# PCB-TBAR-BORADC.net
KiCad netlist of a schematic drawn in EAGLE
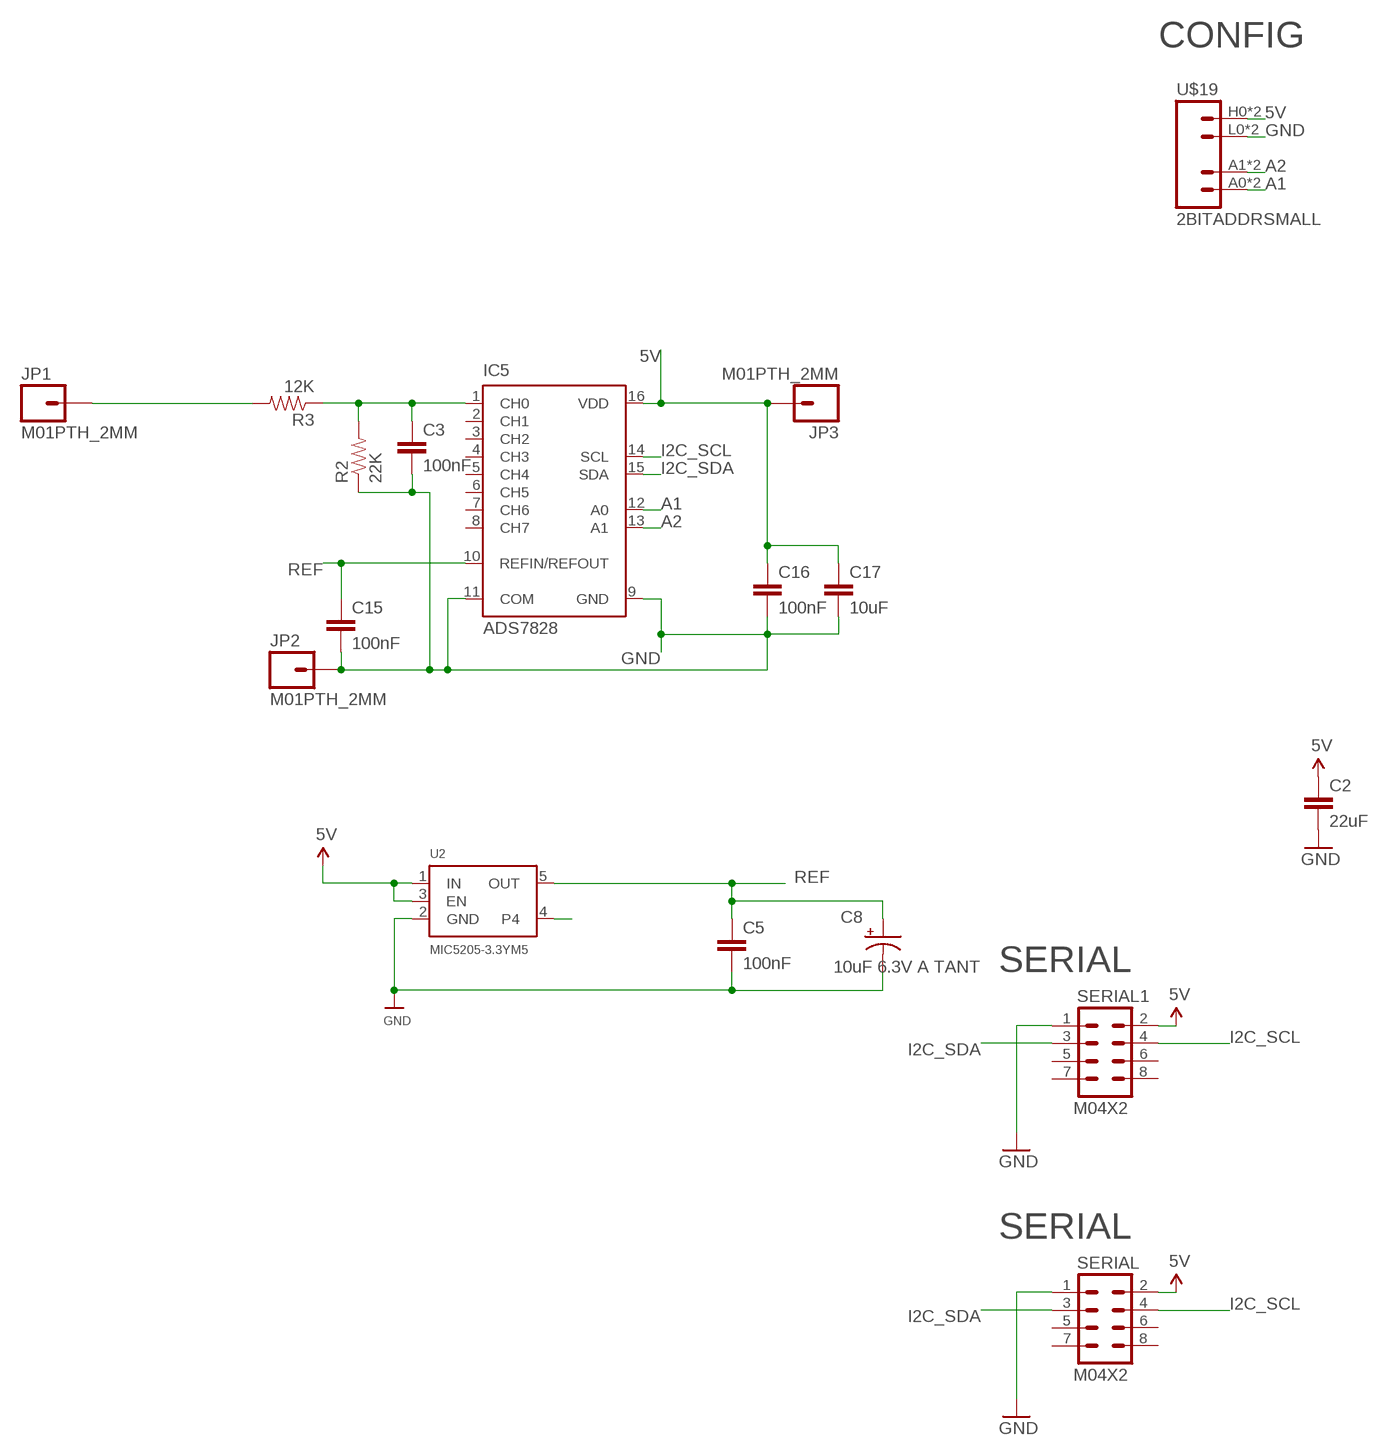
[diagram p0: schematic, sheet 1]

(export (version "E")
  (design (tool "Eeschema 10.0.6"))
  (components
    (comp (ref "C2")
      (value "22uF")
      (footprint "eagle-import:0805")
      (libsource (lib "eagle-import") (part "CAP0805"))
    )
    (comp (ref "C3")
      (value "100nF")
      (footprint "eagle-import:0603-CAP")
      (libsource (lib "eagle-import") (part "CAP0603-CAP"))
    )
    (comp (ref "C5")
      (value "100nF")
      (footprint "eagle-import:0603-CAP")
      (libsource (lib "eagle-import") (part "CAP0603-CAP"))
    )
    (comp (ref "C8")
      (value "10uF 6.3V A TANT")
      (footprint "eagle-import:EIA3216")
      (libsource (lib "eagle-import") (part "CAP_POL1206"))
    )
    (comp (ref "C15")
      (value "100nF")
      (footprint "eagle-import:0603-CAP")
      (libsource (lib "eagle-import") (part "CAP0603-CAP"))
    )
    (comp (ref "C16")
      (value "100nF")
      (footprint "eagle-import:0603-CAP")
      (libsource (lib "eagle-import") (part "CAP0603-CAP"))
    )
    (comp (ref "C17")
      (value "10uF")
      (footprint "eagle-import:0805")
      (libsource (lib "eagle-import") (part "CAP0805"))
    )
    (comp (ref "IC5")
      (value "ADS7828")
      (footprint "eagle-import:TSSOP16-PW")
      (fields (field (name "MF") "TEXAS INSTRUMENTS") (field (name "MPN") "ADS7828E/250"))
      (libsource (lib "eagle-import") (part "ADS7828"))
    )
    (comp (ref "JP1")
      (value "M01PTH_2MM")
      (footprint "eagle-import:1X01_2MM")
      (libsource (lib "eagle-import") (part "M01PTH_2MM"))
    )
    (comp (ref "JP2")
      (value "M01PTH_2MM")
      (footprint "eagle-import:1X01_2MM")
      (libsource (lib "eagle-import") (part "M01PTH_2MM"))
    )
    (comp (ref "JP3")
      (value "M01PTH_2MM")
      (footprint "eagle-import:1X01_2MM")
      (libsource (lib "eagle-import") (part "M01PTH_2MM"))
    )
    (comp (ref "R2")
      (value "22K")
      (footprint "eagle-import:0603-RES")
      (libsource (lib "eagle-import") (part "RESISTOR0603-RES"))
    )
    (comp (ref "R3")
      (value "12K")
      (footprint "eagle-import:0603-RES")
      (libsource (lib "eagle-import") (part "RESISTOR0603-RES"))
    )
    (comp (ref "SERIAL")
      (value "M04X2")
      (footprint "eagle-import:2X4")
      (libsource (lib "eagle-import") (part "M04X2"))
    )
    (comp (ref "SERIAL1")
      (value "M04X2")
      (footprint "eagle-import:2X4")
      (libsource (lib "eagle-import") (part "M04X2"))
    )
    (comp (ref "U$19")
      (value "2BITADDRSMALL")
      (footprint "eagle-import:2BITADDR_SMALL")
      (libsource (lib "eagle-import") (part "2BITADDRSMALL"))
    )
    (comp (ref "U2")
      (value "MIC5205-3.3YM5")
      (footprint "eagle-import:SOT23-5")
      (libsource (lib "eagle-import") (part "VREG_SOT23-5"))
    )
  )
  (nets
    (net (code "1") (name "/A1") (class "Default")
      (node (ref "IC5") (pin "12") (pinfunction "A0_12") (pintype "input"))
      (node (ref "U$19") (pin "A0") (pinfunction "A1_A0") (pintype "passive"))
      (node (ref "U$19") (pin "AS0") (pinfunction "A1_AS0") (pintype "passive"))
    )
    (net (code "2") (name "/A2") (class "Default")
      (node (ref "IC5") (pin "13") (pinfunction "A1_13") (pintype "input"))
      (node (ref "U$19") (pin "A1") (pinfunction "A2_A1") (pintype "passive"))
      (node (ref "U$19") (pin "AS1") (pinfunction "A2_AS1") (pintype "passive"))
    )
    (net (code "3") (name "/I2C_SCL") (class "Default")
      (node (ref "IC5") (pin "14") (pinfunction "SCL_14") (pintype "input"))
      (node (ref "SERIAL") (pin "4") (pinfunction "4_4") (pintype "passive"))
      (node (ref "SERIAL1") (pin "4") (pinfunction "4_4") (pintype "passive"))
    )
    (net (code "4") (name "/I2C_SDA") (class "Default")
      (node (ref "IC5") (pin "15") (pinfunction "SDA_15") (pintype "bidirectional"))
      (node (ref "SERIAL") (pin "3") (pinfunction "3_3") (pintype "passive"))
      (node (ref "SERIAL1") (pin "3") (pinfunction "3_3") (pintype "passive"))
    )
    (net (code "5") (name "/REF") (class "Default")
      (node (ref "C15") (pin "1") (pinfunction "1_1") (pintype "passive"))
      (node (ref "C5") (pin "1") (pinfunction "1_1") (pintype "passive"))
      (node (ref "C8") (pin "A") (pinfunction "+_A") (pintype "passive"))
      (node (ref "IC5") (pin "10") (pinfunction "REFIN/REFOUT_10") (pintype "passive"))
      (node (ref "U2") (pin "5") (pinfunction "OUT_5") (pintype "bidirectional"))
    )
    (net (code "6") (name "5V") (class "Default")
      (node (ref "C16") (pin "1") (pinfunction "1_1") (pintype "passive"))
      (node (ref "C17") (pin "1") (pinfunction "1_1") (pintype "passive"))
      (node (ref "C2") (pin "1") (pinfunction "1_1") (pintype "passive"))
      (node (ref "IC5") (pin "16") (pinfunction "VDD_16") (pintype "power_in"))
      (node (ref "JP3") (pin "1") (pinfunction "1_1") (pintype "passive"))
      (node (ref "SERIAL") (pin "2") (pinfunction "2_2") (pintype "passive"))
      (node (ref "SERIAL1") (pin "2") (pinfunction "2_2") (pintype "passive"))
      (node (ref "U$19") (pin "H0") (pinfunction "VCC_H0") (pintype "passive"))
      (node (ref "U$19") (pin "H1") (pinfunction "VCC_H1") (pintype "passive"))
      (node (ref "U2") (pin "1") (pinfunction "IN_1") (pintype "bidirectional"))
      (node (ref "U2") (pin "3") (pinfunction "EN_3") (pintype "bidirectional"))
    )
    (net (code "7") (name "GND") (class "Default")
      (node (ref "C15") (pin "2") (pinfunction "2_2") (pintype "passive"))
      (node (ref "C16") (pin "2") (pinfunction "2_2") (pintype "passive"))
      (node (ref "C17") (pin "2") (pinfunction "2_2") (pintype "passive"))
      (node (ref "C2") (pin "2") (pinfunction "2_2") (pintype "passive"))
      (node (ref "C3") (pin "2") (pinfunction "2_2") (pintype "passive"))
      (node (ref "C5") (pin "2") (pinfunction "2_2") (pintype "passive"))
      (node (ref "C8") (pin "C") (pinfunction "-_C") (pintype "passive"))
      (node (ref "IC5") (pin "11") (pinfunction "COM_11") (pintype "input"))
      (node (ref "IC5") (pin "9") (pinfunction "GND_9") (pintype "power_in"))
      (node (ref "JP2") (pin "1") (pinfunction "1_1") (pintype "passive"))
      (node (ref "R2") (pin "1") (pinfunction "1_1") (pintype "passive"))
      (node (ref "SERIAL") (pin "1") (pinfunction "1_1") (pintype "passive"))
      (node (ref "SERIAL1") (pin "1") (pinfunction "1_1") (pintype "passive"))
      (node (ref "U$19") (pin "L0") (pinfunction "GND_L0") (pintype "passive"))
      (node (ref "U$19") (pin "L1") (pinfunction "GND_L1") (pintype "passive"))
      (node (ref "U2") (pin "2") (pinfunction "GND_2") (pintype "bidirectional"))
    )
    (net (code "8") (name "Net-(IC5-CH0)") (class "Default")
      (node (ref "C3") (pin "1") (pinfunction "1_1") (pintype "passive"))
      (node (ref "IC5") (pin "1") (pinfunction "CH0_1") (pintype "input"))
      (node (ref "R2") (pin "2") (pinfunction "2_2") (pintype "passive"))
      (node (ref "R3") (pin "1") (pinfunction "1_1") (pintype "passive"))
    )
    (net (code "9") (name "Net-(JP1-Pad1)") (class "Default")
      (node (ref "JP1") (pin "1") (pinfunction "1_1") (pintype "passive"))
      (node (ref "R3") (pin "2") (pinfunction "2_2") (pintype "passive"))
    )
    (net (code "10") (name "unconnected-(IC5-CH1-Pad2)") (class "Default")
      (node (ref "IC5") (pin "2") (pinfunction "CH1_2") (pintype "input"))
    )
    (net (code "11") (name "unconnected-(IC5-CH2-Pad3)") (class "Default")
      (node (ref "IC5") (pin "3") (pinfunction "CH2_3") (pintype "input"))
    )
    (net (code "12") (name "unconnected-(IC5-CH3-Pad4)") (class "Default")
      (node (ref "IC5") (pin "4") (pinfunction "CH3_4") (pintype "input"))
    )
    (net (code "13") (name "unconnected-(IC5-CH4-Pad5)") (class "Default")
      (node (ref "IC5") (pin "5") (pinfunction "CH4_5") (pintype "input"))
    )
    (net (code "14") (name "unconnected-(IC5-CH5-Pad6)") (class "Default")
      (node (ref "IC5") (pin "6") (pinfunction "CH5_6") (pintype "input"))
    )
    (net (code "15") (name "unconnected-(IC5-CH6-Pad7)") (class "Default")
      (node (ref "IC5") (pin "7") (pinfunction "CH6_7") (pintype "input"))
    )
    (net (code "16") (name "unconnected-(IC5-CH7-Pad8)") (class "Default")
      (node (ref "IC5") (pin "8") (pinfunction "CH7_8") (pintype "input"))
    )
    (net (code "17") (name "unconnected-(SERIAL-Pad5)") (class "Default")
      (node (ref "SERIAL") (pin "5") (pinfunction "5_5") (pintype "passive"))
    )
    (net (code "18") (name "unconnected-(SERIAL-Pad6)") (class "Default")
      (node (ref "SERIAL") (pin "6") (pinfunction "6_6") (pintype "passive"))
    )
    (net (code "19") (name "unconnected-(SERIAL-Pad7)") (class "Default")
      (node (ref "SERIAL") (pin "7") (pinfunction "7_7") (pintype "passive"))
    )
    (net (code "20") (name "unconnected-(SERIAL-Pad8)") (class "Default")
      (node (ref "SERIAL") (pin "8") (pinfunction "8_8") (pintype "passive"))
    )
    (net (code "21") (name "unconnected-(SERIAL1-Pad5)") (class "Default")
      (node (ref "SERIAL1") (pin "5") (pinfunction "5_5") (pintype "passive"))
    )
    (net (code "22") (name "unconnected-(SERIAL1-Pad6)") (class "Default")
      (node (ref "SERIAL1") (pin "6") (pinfunction "6_6") (pintype "passive"))
    )
    (net (code "23") (name "unconnected-(SERIAL1-Pad7)") (class "Default")
      (node (ref "SERIAL1") (pin "7") (pinfunction "7_7") (pintype "passive"))
    )
    (net (code "24") (name "unconnected-(SERIAL1-Pad8)") (class "Default")
      (node (ref "SERIAL1") (pin "8") (pinfunction "8_8") (pintype "passive"))
    )
    (net (code "25") (name "unconnected-(U2-P4-Pad4)") (class "Default")
      (node (ref "U2") (pin "4") (pinfunction "P4_4") (pintype "bidirectional"))
    )
  )
)
